# Sheet2.net
KiCad netlist of a schematic drawn in Altium Designer
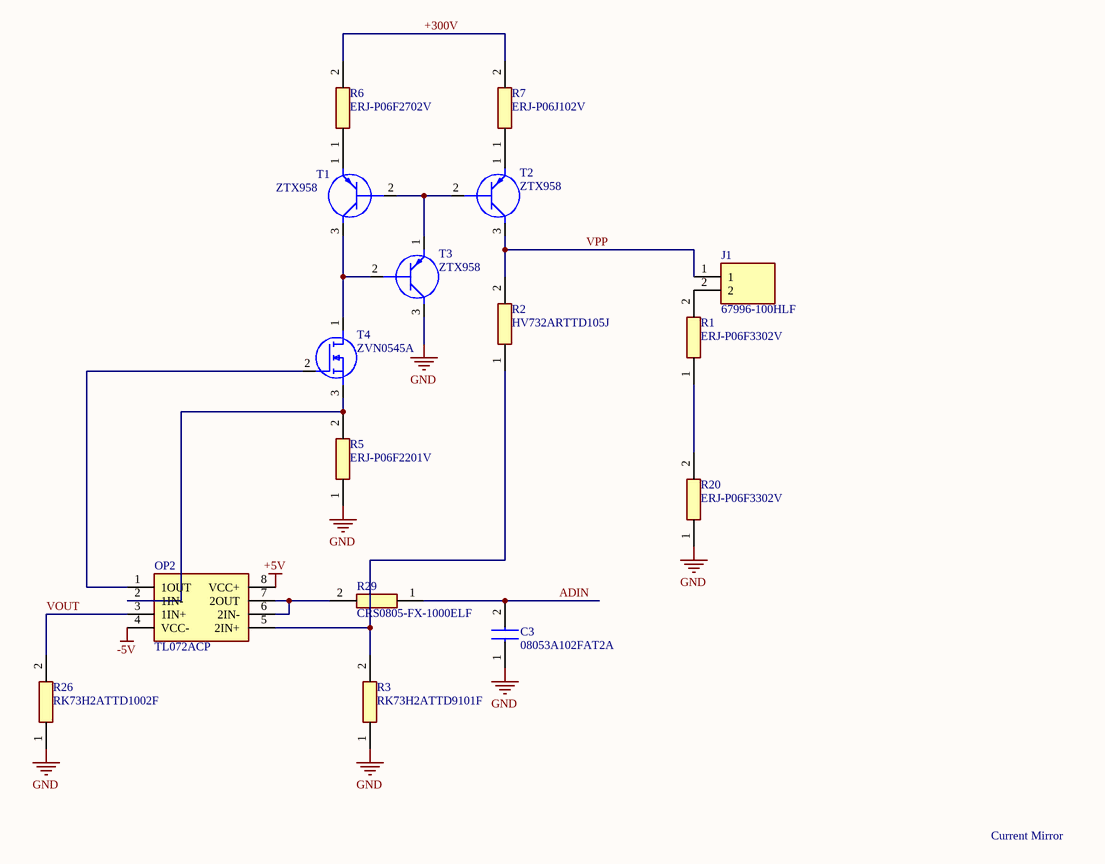
[diagram p0: Sheet2.SchDoc]

(export (version "E")
  (design (tool "Eeschema 10.0.6"))
  (components
    (comp (ref "C3")
      (value "08053A102FAT2A")
      (footprint "SamacSys:CAPC2012X100N")
      (description "Capacitor")
      (fields
        (field (name "MANUFACTURER_PART_NUMBER") "KGM21NR71E104KT")
        (field (name "MOUSER PART NUMBER") "581-KGM21NR71E104KT")
      )
      (libsource (lib "*") (part "KGM21NR71E104KT"))
    )
    (comp (ref "J1")
      (value "67996-100HLF")
      (footprint "HDRV2W67P254_2X1_254X483X858P")
      (libsource (lib "67996-100HLF") (part "67996-100HLF"))
    )
    (comp (ref "OP2")
      (value "TL072ACP")
      (footprint "SamacSys:DIP794W53P254L959H508Q8N")
      (description "Integrated Circuit")
      (fields (field (name "MOUSER PART NUMBER") "595-TL072ACP"))
      (libsource (lib "*") (part "TL072ACP"))
    )
    (comp (ref "R1")
      (value "ERJ-P06F3302V")
      (footprint "SamacSys:RESC2012X60N")
      (description "Resistor")
      (fields (field (name "MANUFACTURER_PART_NUMBER") "RK73B2ATTD123J"))
      (libsource (lib "*") (part "RK73B2ATTD123J"))
    )
    (comp (ref "R2")
      (value "HV732ARTTD105J")
      (footprint "SamacSys:RESC2012X60N")
      (description "Resistor")
      (fields (field (name "MANUFACTURER_PART_NUMBER") "RK73B2ATTD123J"))
      (libsource (lib "*") (part "RK73B2ATTD123J"))
    )
    (comp (ref "R3")
      (value "RK73H2ATTD9101F")
      (footprint "SamacSys:RESC2012X60N")
      (description "Resistor")
      (fields (field (name "MANUFACTURER_PART_NUMBER") "RK73B2ATTD123J"))
      (libsource (lib "*") (part "RK73B2ATTD123J"))
    )
    (comp (ref "R5")
      (value "ERJ-P06F2201V")
      (footprint "SamacSys:RESC2012X60N")
      (description "Resistor")
      (fields (field (name "MANUFACTURER_PART_NUMBER") "RK73B2ATTD123J"))
      (libsource (lib "*") (part "RK73B2ATTD123J"))
    )
    (comp (ref "R6")
      (value "ERJ-P06F2702V")
      (footprint "SamacSys:RESC2012X60N")
      (description "Resistor")
      (fields (field (name "MANUFACTURER_PART_NUMBER") "RK73B2ATTD123J"))
      (libsource (lib "*") (part "RK73B2ATTD123J"))
    )
    (comp (ref "R7")
      (value "ERJ-P06J102V")
      (footprint "SamacSys:RESC2012X60N")
      (description "Resistor")
      (fields (field (name "MANUFACTURER_PART_NUMBER") "RK73B2ATTD123J"))
      (libsource (lib "*") (part "RK73B2ATTD123J"))
    )
    (comp (ref "R20")
      (value "ERJ-P06F3302V")
      (footprint "SamacSys:RESC2012X60N")
      (description "Resistor")
      (fields (field (name "MANUFACTURER_PART_NUMBER") "RK73B2ATTD123J"))
      (libsource (lib "*") (part "RK73B2ATTD123J"))
    )
    (comp (ref "R26")
      (value "RK73H2ATTD1002F")
      (footprint "SamacSys:RESC2012X60N")
      (description "Resistor")
      (fields (field (name "MANUFACTURER_PART_NUMBER") "RK73B2ATTD123J"))
      (libsource (lib "*") (part "RK73B2ATTD123J"))
    )
    (comp (ref "R29")
      (value "CRS0805-FX-1000ELF")
      (footprint "SamacSys:RESC2012X60N")
      (description "Resistor")
      (fields (field (name "MANUFACTURER_PART_NUMBER") "RK73B2ATTD123J"))
      (libsource (lib "") (part "RK73B2ATTD123J_1"))
    )
    (comp (ref "T1")
      (value "ZTX958")
      (footprint "SamacSys:KSP92BU")
      (description "Transistor BJT PNP")
      (fields
        (field (name "MANUFACTURER_PART_NUMBER") "KSP92BU")
        (field (name "MOUSER PART NUMBER") "512-KSP92BU")
      )
      (libsource (lib "*") (part "KSP92BU"))
    )
    (comp (ref "T2")
      (value "ZTX958")
      (footprint "SamacSys:KSP92BU")
      (description "Transistor BJT PNP")
      (fields
        (field (name "MANUFACTURER_PART_NUMBER") "KSP92BU")
        (field (name "MOUSER PART NUMBER") "512-KSP92BU")
      )
      (libsource (lib "*") (part "KSP92BU"))
    )
    (comp (ref "T3")
      (value "ZTX958")
      (footprint "SamacSys:KSP92BU")
      (description "Transistor BJT PNP")
      (fields
        (field (name "MANUFACTURER_PART_NUMBER") "KSP92BU")
        (field (name "MOUSER PART NUMBER") "512-KSP92BU")
      )
      (libsource (lib "*") (part "KSP92BU"))
    )
    (comp (ref "T4")
      (value "ZVN0545A")
      (footprint "SamacSys:BS107P")
      (description "MOSFET (N-Channel)")
      (fields
        (field (name "MANUFACTURER_PART_NUMBER") "BS107P")
        (field (name "MOUSER PART NUMBER") "522-BS107P")
      )
      (libsource (lib "SamacSys") (part "BS107P"))
    )
  )
  (nets
    (net (code "1") (name "+5V") (class "Default")
      (node (ref "OP2") (pin "8") (pinfunction "VCC+_8") (pintype "passive"))
    )
    (net (code "2") (name "-5V") (class "Default")
      (node (ref "OP2") (pin "4") (pinfunction "VCC-_4") (pintype "passive"))
    )
    (net (code "3") (name "/+300V") (class "Default")
      (node (ref "R6") (pin "2") (pinfunction "2_2") (pintype "passive"))
      (node (ref "R7") (pin "2") (pinfunction "2_2") (pintype "passive"))
    )
    (net (code "4") (name "/ADIN") (class "Default")
      (node (ref "C3") (pin "2") (pinfunction "2_2") (pintype "passive"))
      (node (ref "R29") (pin "1") (pinfunction "1_1") (pintype "passive"))
    )
    (net (code "5") (name "/VOUT") (class "Default")
      (node (ref "OP2") (pin "3") (pinfunction "1IN+_3") (pintype "passive"))
      (node (ref "R26") (pin "2") (pinfunction "2_2") (pintype "passive"))
    )
    (net (code "6") (name "/VPP") (class "Default")
      (node (ref "J1") (pin "1") (pinfunction "1_1") (pintype "passive"))
      (node (ref "R2") (pin "2") (pinfunction "2_2") (pintype "passive"))
      (node (ref "T2") (pin "3") (pinfunction "C_3") (pintype "passive"))
    )
    (net (code "7") (name "GND") (class "Default")
      (node (ref "C3") (pin "1") (pinfunction "1_1") (pintype "passive"))
      (node (ref "R20") (pin "1") (pinfunction "1_1") (pintype "passive"))
      (node (ref "R26") (pin "1") (pinfunction "1_1") (pintype "passive"))
      (node (ref "R3") (pin "1") (pinfunction "1_1") (pintype "passive"))
      (node (ref "R5") (pin "1") (pinfunction "1_1") (pintype "passive"))
      (node (ref "T3") (pin "3") (pinfunction "C_3") (pintype "passive"))
    )
    (net (code "8") (name "Net-(J1-Pad2)") (class "Default")
      (node (ref "J1") (pin "2") (pinfunction "2_2") (pintype "passive"))
      (node (ref "R1") (pin "2") (pinfunction "2_2") (pintype "passive"))
    )
    (net (code "9") (name "Net-(OP2-1IN-)") (class "Default")
      (node (ref "OP2") (pin "2") (pinfunction "1IN-_2") (pintype "passive"))
      (node (ref "R5") (pin "2") (pinfunction "2_2") (pintype "passive"))
      (node (ref "T4") (pin "3") (pinfunction "S_3") (pintype "passive"))
    )
    (net (code "10") (name "Net-(OP2-1OUT)") (class "Default")
      (node (ref "OP2") (pin "1") (pinfunction "1OUT_1") (pintype "passive"))
      (node (ref "T4") (pin "2") (pinfunction "G_2") (pintype "passive"))
    )
    (net (code "11") (name "Net-(OP2-2IN+)") (class "Default")
      (node (ref "OP2") (pin "5") (pinfunction "2IN+_5") (pintype "passive"))
      (node (ref "R2") (pin "1") (pinfunction "1_1") (pintype "passive"))
      (node (ref "R3") (pin "2") (pinfunction "2_2") (pintype "passive"))
    )
    (net (code "12") (name "Net-(OP2-2IN-)") (class "Default")
      (node (ref "OP2") (pin "6") (pinfunction "2IN-_6") (pintype "passive"))
      (node (ref "OP2") (pin "7") (pinfunction "2OUT_7") (pintype "passive"))
      (node (ref "R29") (pin "2") (pinfunction "2_2") (pintype "passive"))
    )
    (net (code "13") (name "Net-(R1-Pad1)") (class "Default")
      (node (ref "R1") (pin "1") (pinfunction "1_1") (pintype "passive"))
      (node (ref "R20") (pin "2") (pinfunction "2_2") (pintype "passive"))
    )
    (net (code "14") (name "Net-(T1-B)") (class "Default")
      (node (ref "T1") (pin "2") (pinfunction "B_2") (pintype "passive"))
      (node (ref "T2") (pin "2") (pinfunction "B_2") (pintype "passive"))
      (node (ref "T3") (pin "1") (pinfunction "E_1") (pintype "passive"))
    )
    (net (code "15") (name "Net-(T1-C)") (class "Default")
      (node (ref "T1") (pin "3") (pinfunction "C_3") (pintype "passive"))
      (node (ref "T3") (pin "2") (pinfunction "B_2") (pintype "passive"))
      (node (ref "T4") (pin "1") (pinfunction "D_1") (pintype "passive"))
    )
    (net (code "16") (name "Net-(T1-E)") (class "Default")
      (node (ref "R6") (pin "1") (pinfunction "1_1") (pintype "passive"))
      (node (ref "T1") (pin "1") (pinfunction "E_1") (pintype "passive"))
    )
    (net (code "17") (name "Net-(T2-E)") (class "Default")
      (node (ref "R7") (pin "1") (pinfunction "1_1") (pintype "passive"))
      (node (ref "T2") (pin "1") (pinfunction "E_1") (pintype "passive"))
    )
  )
)
